# Power.net
KiCad netlist of a schematic drawn in Altium Designer
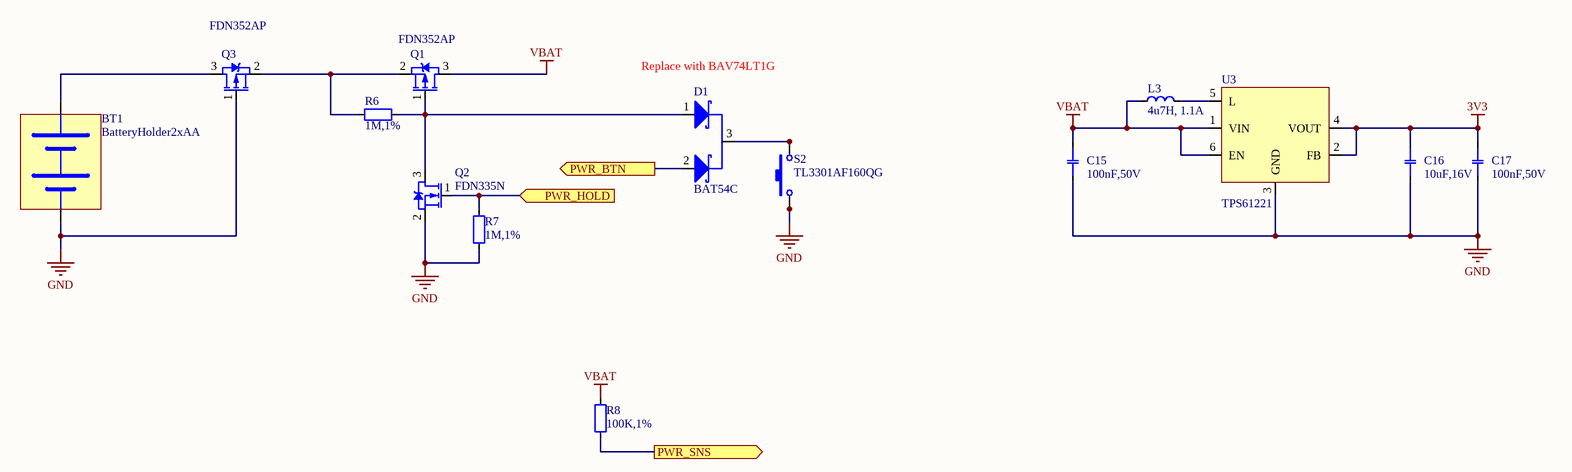
[diagram p0: Power.SchDoc]

(export (version "E")
  (design (tool "Eeschema 10.0.6"))
  (components
    (comp (ref "BT1")
      (value "BatteryHolder2xAA")
      (footprint "BATTERY_HOLDER_2AA")
      (libsource (lib "Common") (part "BatteryHolder2xAA"))
    )
    (comp (ref "C15")
      (value "100nF,50V")
      (footprint "CAPC1608X09N_0603")
      (description "CAP CER 0.1UF 50V 10% X7R 0603")
      (fields (field (name "MANUFACTURER") "Kemet") (field (name "TOLERANCE") "10%"))
      (libsource (lib "library") (part "CAP-NP_1"))
    )
    (comp (ref "C16")
      (value "10uF,16V")
      (footprint "CAPC2012X12N_0805")
      (description "CAP CER 10µF ±10% 16V X7R 0805")
      (fields
        (field (name "MANUFACTURER") "Samsung Electro-Mechanics America, Inc.")
        (field (name "TOLERANCE") "10%")
      )
      (libsource (lib "library") (part "CAP-NP_1"))
    )
    (comp (ref "C17")
      (value "100nF,50V")
      (footprint "CAPC1608X09N_0603")
      (description "CAP CER 0.1UF 50V 10% X7R 0603")
      (fields (field (name "MANUFACTURER") "Kemet") (field (name "TOLERANCE") "10%"))
      (libsource (lib "library") (part "CAP-NP_1"))
    )
    (comp (ref "D1")
      (value "BAT54C")
      (footprint "SOT95P237X111-3N_SOT23")
      (description "DIODE ARRAY SCHOTTKY 30V SOT23-3")
      (fields (field (name "MANUFACTURER") "Fairchild/ON Semiconductor"))
      (libsource (lib "library") (part "BAT54C"))
    )
    (comp (ref "L3")
      (value "4u7H, 1.1A")
      (footprint "INDC2520X12N_1008")
      (description "INDUCTOR POWER 4.7UH 1.1A SMD")
      (fields
        (field (name "MANUFACTURER") "Murata Electronics North America")
        (field (name "MANUFACTURER PART NUMBER") "DFE252010R-H-4R7M=P2")
      )
      (libsource (lib "library") (part "INDUCTOR_1"))
    )
    (comp (ref "Q1")
      (value "FDN352AP")
      (footprint "SOT95P230X110-3N_SOT23")
      (description "MOSFET P-CH 30V 1.3A SSOT-3")
      (fields (field (name "MANUFACTURER") "Fairchild"))
      (libsource (lib "library") (part "MOSFET-P_1"))
    )
    (comp (ref "Q2")
      (value "FDN335N")
      (footprint "SOT95P230X110-3N_SOT23")
      (description "MOSFET N-CH 20V 1.7A SSOT3")
      (fields (field (name "MANUFACTURER") "Fairchild Semiconductor"))
      (libsource (lib "library") (part "MOSFET-N_1"))
    )
    (comp (ref "Q3")
      (value "FDN352AP")
      (footprint "SOT95P230X110-3N_SOT23")
      (description "MOSFET P-CH 30V 1.3A SSOT-3")
      (fields (field (name "MANUFACTURER") "Fairchild"))
      (libsource (lib "library") (part "MOSFET-P_1"))
    )
    (comp (ref "R6")
      (value "1M,1%")
      (footprint "RESC1608X06N_0603")
      (description "RES 1.00M OHM 1/10W 1% 0603 SMD")
      (fields (field (name "MANUFACTURER") "Yageo") (field (name "POWER") "0.1W"))
      (libsource (lib "") (part "RESISTOR_1_2"))
    )
    (comp (ref "R7")
      (value "1M,1%")
      (footprint "RESC1608X06N_0603")
      (description "RES 1.00M OHM 1/10W 1% 0603 SMD")
      (fields (field (name "MANUFACTURER") "Yageo") (field (name "POWER") "0.1W"))
      (libsource (lib "library") (part "RESISTOR_1"))
    )
    (comp (ref "R8")
      (value "100K,1%")
      (footprint "RESC1608X06N_0603")
      (description "RES 100K OHM 1/10W 1% 0603 SMD")
      (fields (field (name "MANUFACTURER") "Yageo") (field (name "POWER") "0.1W"))
      (libsource (lib "") (part "RESISTOR_1_1"))
    )
    (comp (ref "S2")
      (value "TL3301AF160QG")
      (footprint "SW_TL3301AFXXXXG")
      (description "SWITCH TACT 160GF H=5.0MM SMT")
      (fields (field (name "MANUFACTURER") "E-Switch"))
      (libsource (lib "library") (part "SW_SPST_2"))
    )
    (comp (ref "U3")
      (value "TPS61221")
      (footprint "TSOP65P210X100-6N_SC70")
      (description "IC REG BOOST 3.3V 200MA SC70-6")
      (fields
        (field (name "MANUFACTURER") "Texas Instruments")
        (field (name "MANUFACTURER PART NUMBER") "TPS61221DCKT")
      )
      (libsource (lib "library") (part "TPS61221"))
    )
  )
  (nets
    (net (code "1") (name "/PWR_BTN") (class "Default")
      (node (ref "D1") (pin "2") (pinfunction "A2_2") (pintype "passive"))
    )
    (net (code "2") (name "/PWR_HOLD") (class "Default")
      (node (ref "Q2") (pin "1") (pinfunction "G_1") (pintype "passive"))
      (node (ref "R7") (pin "1") (pinfunction "1_1") (pintype "passive"))
    )
    (net (code "3") (name "/PWR_SNS") (class "Default")
      (node (ref "R8") (pin "1") (pinfunction "1_1") (pintype "passive"))
    )
    (net (code "4") (name "3V3") (class "Default")
      (node (ref "C16") (pin "2") (pinfunction "2_2") (pintype "passive"))
      (node (ref "C17") (pin "2") (pinfunction "2_2") (pintype "passive"))
      (node (ref "U3") (pin "2") (pinfunction "FB_2") (pintype "passive"))
      (node (ref "U3") (pin "4") (pinfunction "VOUT_4") (pintype "passive"))
    )
    (net (code "5") (name "GND") (class "Default")
      (node (ref "BT1") (pin "2") (pinfunction "-_2") (pintype "passive"))
      (node (ref "C15") (pin "1") (pinfunction "1_1") (pintype "passive"))
      (node (ref "C16") (pin "1") (pinfunction "1_1") (pintype "passive"))
      (node (ref "C17") (pin "1") (pinfunction "1_1") (pintype "passive"))
      (node (ref "Q2") (pin "2") (pinfunction "S_2") (pintype "passive"))
      (node (ref "Q3") (pin "1") (pinfunction "G_1") (pintype "passive"))
      (node (ref "R7") (pin "2") (pinfunction "2_2") (pintype "passive"))
      (node (ref "S2") (pin "1") (pinfunction "1_1") (pintype "passive"))
      (node (ref "S2") (pin "2") (pinfunction "2_2") (pintype "passive"))
      (node (ref "U3") (pin "3") (pinfunction "GND_3") (pintype "passive"))
    )
    (net (code "6") (name "Net-(BT1-+)") (class "Default")
      (node (ref "BT1") (pin "1") (pinfunction "+_1") (pintype "passive"))
      (node (ref "Q3") (pin "3") (pinfunction "D_3") (pintype "passive"))
    )
    (net (code "7") (name "Net-(D1-A1)") (class "Default")
      (node (ref "D1") (pin "1") (pinfunction "A1_1") (pintype "passive"))
      (node (ref "Q1") (pin "1") (pinfunction "G_1") (pintype "passive"))
      (node (ref "Q2") (pin "3") (pinfunction "D_3") (pintype "passive"))
      (node (ref "R6") (pin "1") (pinfunction "1_1") (pintype "passive"))
    )
    (net (code "8") (name "Net-(D1-C1{slash}C2)") (class "Default")
      (node (ref "D1") (pin "3") (pinfunction "C1/C2_3") (pintype "passive"))
      (node (ref "S2") (pin "3") (pinfunction "3_3") (pintype "passive"))
      (node (ref "S2") (pin "4") (pinfunction "4_4") (pintype "passive"))
    )
    (net (code "9") (name "Net-(Q1-S)") (class "Default")
      (node (ref "Q1") (pin "2") (pinfunction "S_2") (pintype "passive"))
      (node (ref "Q3") (pin "2") (pinfunction "S_2") (pintype "passive"))
      (node (ref "R6") (pin "2") (pinfunction "2_2") (pintype "passive"))
    )
    (net (code "10") (name "Net-(U3-L)") (class "Default")
      (node (ref "L3") (pin "2") (pinfunction "2_2") (pintype "passive"))
      (node (ref "U3") (pin "5") (pinfunction "L_5") (pintype "passive"))
    )
    (net (code "11") (name "VBAT") (class "Default")
      (node (ref "C15") (pin "2") (pinfunction "2_2") (pintype "passive"))
      (node (ref "L3") (pin "1") (pinfunction "1_1") (pintype "passive"))
      (node (ref "Q1") (pin "3") (pinfunction "D_3") (pintype "passive"))
      (node (ref "R8") (pin "2") (pinfunction "2_2") (pintype "passive"))
      (node (ref "U3") (pin "1") (pinfunction "VIN_1") (pintype "passive"))
      (node (ref "U3") (pin "6") (pinfunction "EN_6") (pintype "passive"))
    )
  )
)
